# atmega328p.net
KiCad netlist of a schematic drawn in EAGLE
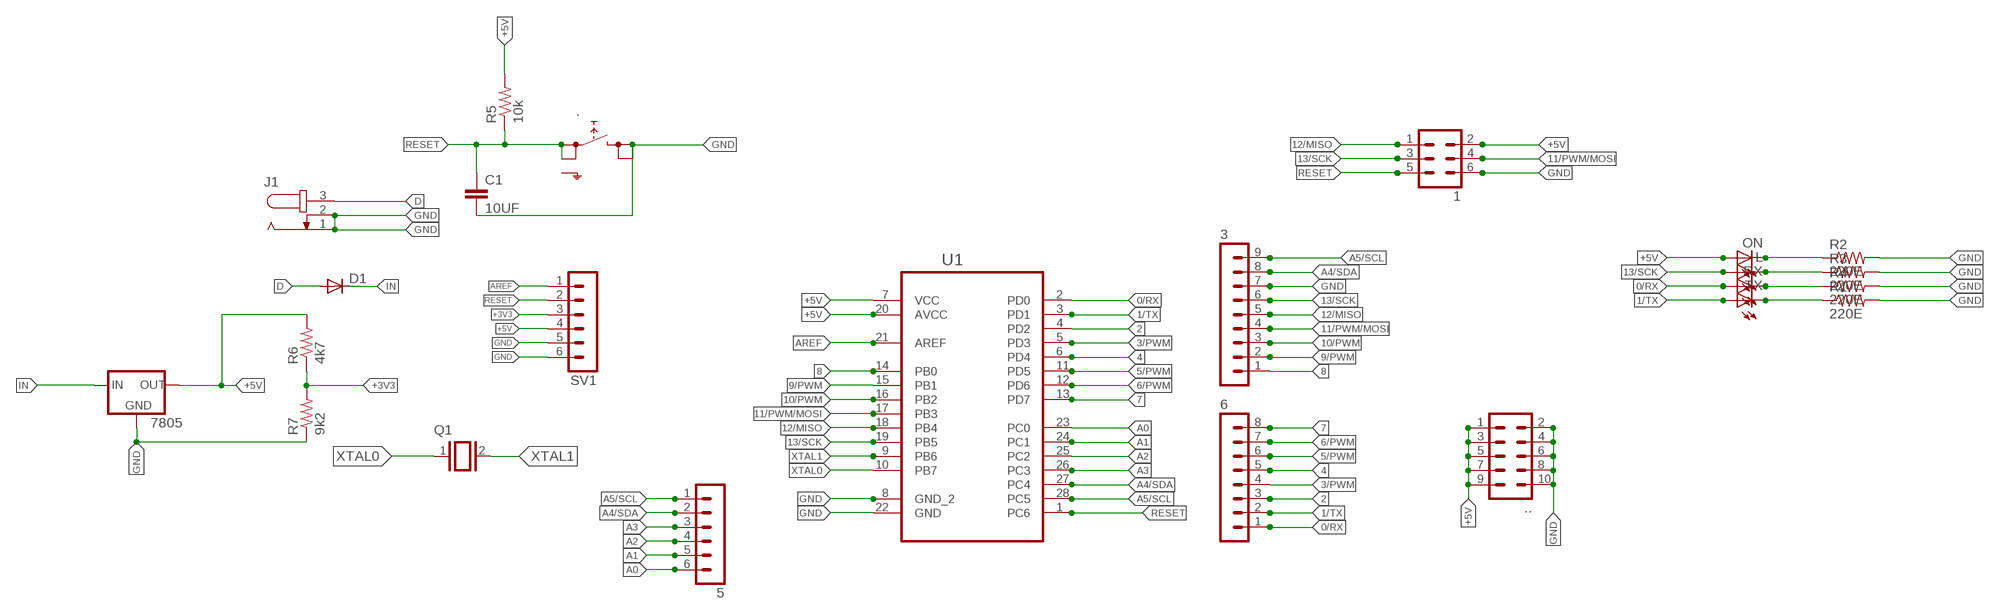
[diagram p0: schematic, sheet 1]

(export (version "E")
  (design (tool "Eeschema 10.0.6"))
  (components
    (comp (ref ".")
      (value "SKHMPSE010")
      (footprint "eagle-import:SKHMPXE010")
      (libsource (lib "eagle-import") (part "SKHMPE010S"))
    )
    (comp (ref "..")
      (value "MA05-2")
      (footprint "eagle-import:MA05-2")
      (libsource (lib "eagle-import") (part "MA05-2"))
    )
    (comp (ref "1")
      (value "MA03-2")
      (footprint "eagle-import:MA03-2")
      (libsource (lib "eagle-import") (part "MA03-2"))
    )
    (comp (ref "3")
      (value "MA09-1")
      (footprint "eagle-import:MA09-1")
      (libsource (lib "eagle-import") (part "MA09-1"))
    )
    (comp (ref "5")
      (value "MA06-1")
      (footprint "eagle-import:MA06-1")
      (libsource (lib "eagle-import") (part "MA06-1"))
    )
    (comp (ref "6")
      (value "MA08-1")
      (footprint "eagle-import:MA08-1")
      (libsource (lib "eagle-import") (part "MA08-1"))
    )
    (comp (ref "7805")
      (value "78XXS")
      (footprint "eagle-import:78XXS")
      (libsource (lib "eagle-import") (part "78XXS"))
    )
    (comp (ref "C1")
      (value "10UF")
      (footprint "eagle-import:C025-025X050")
      (libsource (lib "eagle-import") (part "C-EU025-025X050"))
    )
    (comp (ref "D1")
      (value "1N4004")
      (footprint "eagle-import:DO41-10")
      (libsource (lib "eagle-import") (part "1N4004"))
    )
    (comp (ref "J1")
      (value "JACK-PLUG0")
      (footprint "eagle-import:SPC4077")
      (libsource (lib "eagle-import") (part "JACK-PLUG0"))
    )
    (comp (ref "L")
      (value "LEDCHIP-LED0805")
      (footprint "eagle-import:CHIP-LED0805")
      (libsource (lib "eagle-import") (part "LEDCHIP-LED0805"))
    )
    (comp (ref "ON")
      (value "LEDCHIP-LED0805")
      (footprint "eagle-import:CHIP-LED0805")
      (libsource (lib "eagle-import") (part "LEDCHIP-LED0805"))
    )
    (comp (ref "Q1")
      (value "XTAL/S")
      (footprint "eagle-import:QS")
      (libsource (lib "eagle-import") (part "XTAL/S"))
    )
    (comp (ref "R1")
      (value "220E")
      (footprint "eagle-import:0204_7")
      (libsource (lib "eagle-import") (part "R-US_0204/7"))
    )
    (comp (ref "R2")
      (value "220E")
      (footprint "eagle-import:0204_7")
      (libsource (lib "eagle-import") (part "R-US_0204/7"))
    )
    (comp (ref "R3")
      (value "220E")
      (footprint "eagle-import:0204_7")
      (libsource (lib "eagle-import") (part "R-US_0204/7"))
    )
    (comp (ref "R4")
      (value "220E")
      (footprint "eagle-import:0204_7")
      (libsource (lib "eagle-import") (part "R-US_0204/7"))
    )
    (comp (ref "R5")
      (value "10k")
      (footprint "eagle-import:0204_7")
      (libsource (lib "eagle-import") (part "R-US_0204/7"))
    )
    (comp (ref "R6")
      (value "4k7")
      (footprint "eagle-import:0204_7")
      (libsource (lib "eagle-import") (part "R-US_0204/7"))
    )
    (comp (ref "R7")
      (value "9k2")
      (footprint "eagle-import:0204_7")
      (libsource (lib "eagle-import") (part "R-US_0204/7"))
    )
    (comp (ref "RX")
      (value "LEDCHIP-LED0805")
      (footprint "eagle-import:CHIP-LED0805")
      (libsource (lib "eagle-import") (part "LEDCHIP-LED0805"))
    )
    (comp (ref "SV1")
      (value "MA06-1")
      (footprint "eagle-import:MA06-1")
      (libsource (lib "eagle-import") (part "MA06-1"))
    )
    (comp (ref "TX")
      (value "LEDCHIP-LED0805")
      (footprint "eagle-import:CHIP-LED0805")
      (libsource (lib "eagle-import") (part "LEDCHIP-LED0805"))
    )
    (comp (ref "U1")
      (value "ATMEGA328P-PU")
      (footprint "eagle-import:DIP254P762X457-28")
      (libsource (lib "eagle-import") (part "ATMEGA328P-PU"))
    )
  )
  (nets
    (net (code "1") (name "+3V3") (class "Default")
      (node (ref "R6") (pin "1") (pinfunction "1_1") (pintype "passive"))
      (node (ref "R7") (pin "2") (pinfunction "2_2") (pintype "passive"))
      (node (ref "SV1") (pin "3") (pinfunction "3_3") (pintype "passive"))
    )
    (net (code "2") (name "+5V") (class "Default")
      (node (ref "..") (pin "1") (pinfunction "1_1") (pintype "passive"))
      (node (ref "..") (pin "3") (pinfunction "3_3") (pintype "passive"))
      (node (ref "..") (pin "5") (pinfunction "5_5") (pintype "passive"))
      (node (ref "..") (pin "7") (pinfunction "7_7") (pintype "passive"))
      (node (ref "..") (pin "9") (pinfunction "9_9") (pintype "passive"))
      (node (ref "1") (pin "2") (pinfunction "2_2") (pintype "passive"))
      (node (ref "7805") (pin "OUT") (pinfunction "OUT_OUT") (pintype "passive"))
      (node (ref "ON") (pin "A") (pinfunction "A_A") (pintype "passive"))
      (node (ref "R5") (pin "2") (pinfunction "2_2") (pintype "passive"))
      (node (ref "R6") (pin "2") (pinfunction "2_2") (pintype "passive"))
      (node (ref "SV1") (pin "4") (pinfunction "4_4") (pintype "passive"))
      (node (ref "U1") (pin "20") (pinfunction "AVCC_20") (pintype "power_in"))
      (node (ref "U1") (pin "7") (pinfunction "VCC_7") (pintype "power_in"))
    )
    (net (code "3") (name "0{slash}RX") (class "Default")
      (node (ref "6") (pin "1") (pinfunction "1_1") (pintype "passive"))
      (node (ref "RX") (pin "A") (pinfunction "A_A") (pintype "passive"))
      (node (ref "U1") (pin "2") (pinfunction "PD0_2") (pintype "bidirectional"))
    )
    (net (code "4") (name "1{slash}TX") (class "Default")
      (node (ref "6") (pin "2") (pinfunction "2_2") (pintype "passive"))
      (node (ref "TX") (pin "A") (pinfunction "A_A") (pintype "passive"))
      (node (ref "U1") (pin "3") (pinfunction "PD1_3") (pintype "bidirectional"))
    )
    (net (code "5") (name "2") (class "Default")
      (node (ref "6") (pin "3") (pinfunction "3_3") (pintype "passive"))
      (node (ref "U1") (pin "4") (pinfunction "PD2_4") (pintype "bidirectional"))
    )
    (net (code "6") (name "3{slash}PWM") (class "Default")
      (node (ref "6") (pin "4") (pinfunction "4_4") (pintype "passive"))
      (node (ref "U1") (pin "5") (pinfunction "PD3_5") (pintype "bidirectional"))
    )
    (net (code "7") (name "4") (class "Default")
      (node (ref "6") (pin "5") (pinfunction "5_5") (pintype "passive"))
      (node (ref "U1") (pin "6") (pinfunction "PD4_6") (pintype "bidirectional"))
    )
    (net (code "8") (name "5{slash}PWM") (class "Default")
      (node (ref "6") (pin "6") (pinfunction "6_6") (pintype "passive"))
      (node (ref "U1") (pin "11") (pinfunction "PD5_11") (pintype "bidirectional"))
    )
    (net (code "9") (name "6{slash}PWM") (class "Default")
      (node (ref "6") (pin "7") (pinfunction "7_7") (pintype "passive"))
      (node (ref "U1") (pin "12") (pinfunction "PD6_12") (pintype "bidirectional"))
    )
    (net (code "10") (name "7") (class "Default")
      (node (ref "6") (pin "8") (pinfunction "8_8") (pintype "passive"))
      (node (ref "U1") (pin "13") (pinfunction "PD7_13") (pintype "bidirectional"))
    )
    (net (code "11") (name "8") (class "Default")
      (node (ref "3") (pin "1") (pinfunction "1_1") (pintype "passive"))
      (node (ref "U1") (pin "14") (pinfunction "PB0_14") (pintype "bidirectional"))
    )
    (net (code "12") (name "9{slash}PWM") (class "Default")
      (node (ref "3") (pin "2") (pinfunction "2_2") (pintype "passive"))
      (node (ref "U1") (pin "15") (pinfunction "PB1_15") (pintype "bidirectional"))
    )
    (net (code "13") (name "10{slash}PWM") (class "Default")
      (node (ref "3") (pin "3") (pinfunction "3_3") (pintype "passive"))
      (node (ref "U1") (pin "16") (pinfunction "PB2_16") (pintype "bidirectional"))
    )
    (net (code "14") (name "11{slash}PWM{slash}MOSI") (class "Default")
      (node (ref "1") (pin "4") (pinfunction "4_4") (pintype "passive"))
      (node (ref "3") (pin "4") (pinfunction "4_4") (pintype "passive"))
      (node (ref "U1") (pin "17") (pinfunction "PB3_17") (pintype "bidirectional"))
    )
    (net (code "15") (name "12{slash}MISO") (class "Default")
      (node (ref "1") (pin "1") (pinfunction "1_1") (pintype "passive"))
      (node (ref "3") (pin "5") (pinfunction "5_5") (pintype "passive"))
      (node (ref "U1") (pin "18") (pinfunction "PB4_18") (pintype "bidirectional"))
    )
    (net (code "16") (name "13{slash}SCK") (class "Default")
      (node (ref "1") (pin "3") (pinfunction "3_3") (pintype "passive"))
      (node (ref "3") (pin "6") (pinfunction "6_6") (pintype "passive"))
      (node (ref "L") (pin "A") (pinfunction "A_A") (pintype "passive"))
      (node (ref "U1") (pin "19") (pinfunction "PB5_19") (pintype "bidirectional"))
    )
    (net (code "17") (name "A0") (class "Default")
      (node (ref "5") (pin "6") (pinfunction "6_6") (pintype "passive"))
      (node (ref "U1") (pin "23") (pinfunction "PC0_23") (pintype "bidirectional"))
    )
    (net (code "18") (name "A1") (class "Default")
      (node (ref "5") (pin "5") (pinfunction "5_5") (pintype "passive"))
      (node (ref "U1") (pin "24") (pinfunction "PC1_24") (pintype "bidirectional"))
    )
    (net (code "19") (name "A2") (class "Default")
      (node (ref "5") (pin "4") (pinfunction "4_4") (pintype "passive"))
      (node (ref "U1") (pin "25") (pinfunction "PC2_25") (pintype "bidirectional"))
    )
    (net (code "20") (name "A3") (class "Default")
      (node (ref "5") (pin "3") (pinfunction "3_3") (pintype "passive"))
      (node (ref "U1") (pin "26") (pinfunction "PC3_26") (pintype "bidirectional"))
    )
    (net (code "21") (name "A4{slash}SDA") (class "Default")
      (node (ref "3") (pin "8") (pinfunction "8_8") (pintype "passive"))
      (node (ref "5") (pin "2") (pinfunction "2_2") (pintype "passive"))
      (node (ref "U1") (pin "27") (pinfunction "PC4_27") (pintype "bidirectional"))
    )
    (net (code "22") (name "A5{slash}SCL") (class "Default")
      (node (ref "3") (pin "9") (pinfunction "9_9") (pintype "passive"))
      (node (ref "5") (pin "1") (pinfunction "1_1") (pintype "passive"))
      (node (ref "U1") (pin "28") (pinfunction "PC5_28") (pintype "bidirectional"))
    )
    (net (code "23") (name "AREF") (class "Default")
      (node (ref "SV1") (pin "1") (pinfunction "1_1") (pintype "passive"))
      (node (ref "U1") (pin "21") (pinfunction "AREF_21") (pintype "input"))
    )
    (net (code "24") (name "D") (class "Default")
      (node (ref "D1") (pin "A") (pinfunction "A_A") (pintype "passive"))
      (node (ref "J1") (pin "3") (pinfunction "3_3") (pintype "passive"))
    )
    (net (code "25") (name "GND") (class "Default")
      (node (ref ".") (pin "3") (pinfunction "2.1_3") (pintype "passive"))
      (node (ref ".") (pin "4") (pinfunction "2.2_4") (pintype "passive"))
      (node (ref "..") (pin "10") (pinfunction "10_10") (pintype "passive"))
      (node (ref "..") (pin "2") (pinfunction "2_2") (pintype "passive"))
      (node (ref "..") (pin "4") (pinfunction "4_4") (pintype "passive"))
      (node (ref "..") (pin "6") (pinfunction "6_6") (pintype "passive"))
      (node (ref "..") (pin "8") (pinfunction "8_8") (pintype "passive"))
      (node (ref "1") (pin "6") (pinfunction "6_6") (pintype "passive"))
      (node (ref "3") (pin "7") (pinfunction "7_7") (pintype "passive"))
      (node (ref "7805") (pin "GND") (pinfunction "GND_GND") (pintype "input"))
      (node (ref "C1") (pin "2") (pinfunction "2_2") (pintype "passive"))
      (node (ref "J1") (pin "1") (pinfunction "1_1") (pintype "passive"))
      (node (ref "J1") (pin "2") (pinfunction "2_2") (pintype "passive"))
      (node (ref "R1") (pin "2") (pinfunction "2_2") (pintype "passive"))
      (node (ref "R2") (pin "2") (pinfunction "2_2") (pintype "passive"))
      (node (ref "R3") (pin "2") (pinfunction "2_2") (pintype "passive"))
      (node (ref "R4") (pin "2") (pinfunction "2_2") (pintype "passive"))
      (node (ref "R7") (pin "1") (pinfunction "1_1") (pintype "passive"))
      (node (ref "SV1") (pin "5") (pinfunction "5_5") (pintype "passive"))
      (node (ref "SV1") (pin "6") (pinfunction "6_6") (pintype "passive"))
      (node (ref "U1") (pin "22") (pinfunction "GND_22") (pintype "passive"))
      (node (ref "U1") (pin "8") (pinfunction "GND_2_8") (pintype "passive"))
    )
    (net (code "26") (name "IN") (class "Default")
      (node (ref "7805") (pin "IN") (pinfunction "IN_IN") (pintype "input"))
      (node (ref "D1") (pin "C") (pinfunction "C_C") (pintype "passive"))
    )
    (net (code "27") (name "Net-(L-PadC)") (class "Default")
      (node (ref "L") (pin "C") (pinfunction "C_C") (pintype "passive"))
      (node (ref "R3") (pin "1") (pinfunction "1_1") (pintype "passive"))
    )
    (net (code "28") (name "Net-(ON-PadC)") (class "Default")
      (node (ref "ON") (pin "C") (pinfunction "C_C") (pintype "passive"))
      (node (ref "R2") (pin "1") (pinfunction "1_1") (pintype "passive"))
    )
    (net (code "29") (name "Net-(R1-Pad1)") (class "Default")
      (node (ref "R1") (pin "1") (pinfunction "1_1") (pintype "passive"))
      (node (ref "TX") (pin "C") (pinfunction "C_C") (pintype "passive"))
    )
    (net (code "30") (name "Net-(R4-Pad1)") (class "Default")
      (node (ref "R4") (pin "1") (pinfunction "1_1") (pintype "passive"))
      (node (ref "RX") (pin "C") (pinfunction "C_C") (pintype "passive"))
    )
    (net (code "31") (name "RESET") (class "Default")
      (node (ref ".") (pin "1") (pinfunction "1.1_1") (pintype "passive"))
      (node (ref ".") (pin "2") (pinfunction "1.2_2") (pintype "passive"))
      (node (ref "1") (pin "5") (pinfunction "5_5") (pintype "passive"))
      (node (ref "C1") (pin "1") (pinfunction "1_1") (pintype "passive"))
      (node (ref "R5") (pin "1") (pinfunction "1_1") (pintype "passive"))
      (node (ref "SV1") (pin "2") (pinfunction "2_2") (pintype "passive"))
      (node (ref "U1") (pin "1") (pinfunction "PC6_1") (pintype "bidirectional"))
    )
    (net (code "32") (name "XTAL0") (class "Default")
      (node (ref "Q1") (pin "1") (pinfunction "1_1") (pintype "passive"))
      (node (ref "U1") (pin "10") (pinfunction "PB7_10") (pintype "bidirectional"))
    )
    (net (code "33") (name "XTAL1") (class "Default")
      (node (ref "Q1") (pin "2") (pinfunction "2_2") (pintype "passive"))
      (node (ref "U1") (pin "9") (pinfunction "PB6_9") (pintype "bidirectional"))
    )
    (net (code "34") (name "unconnected-(.-SH-Pad5)") (class "Default")
      (node (ref ".") (pin "5") (pinfunction "SH_5") (pintype "passive"))
    )
  )
)
